# untitled.net
KiCad netlist of a schematic drawn in EAGLE
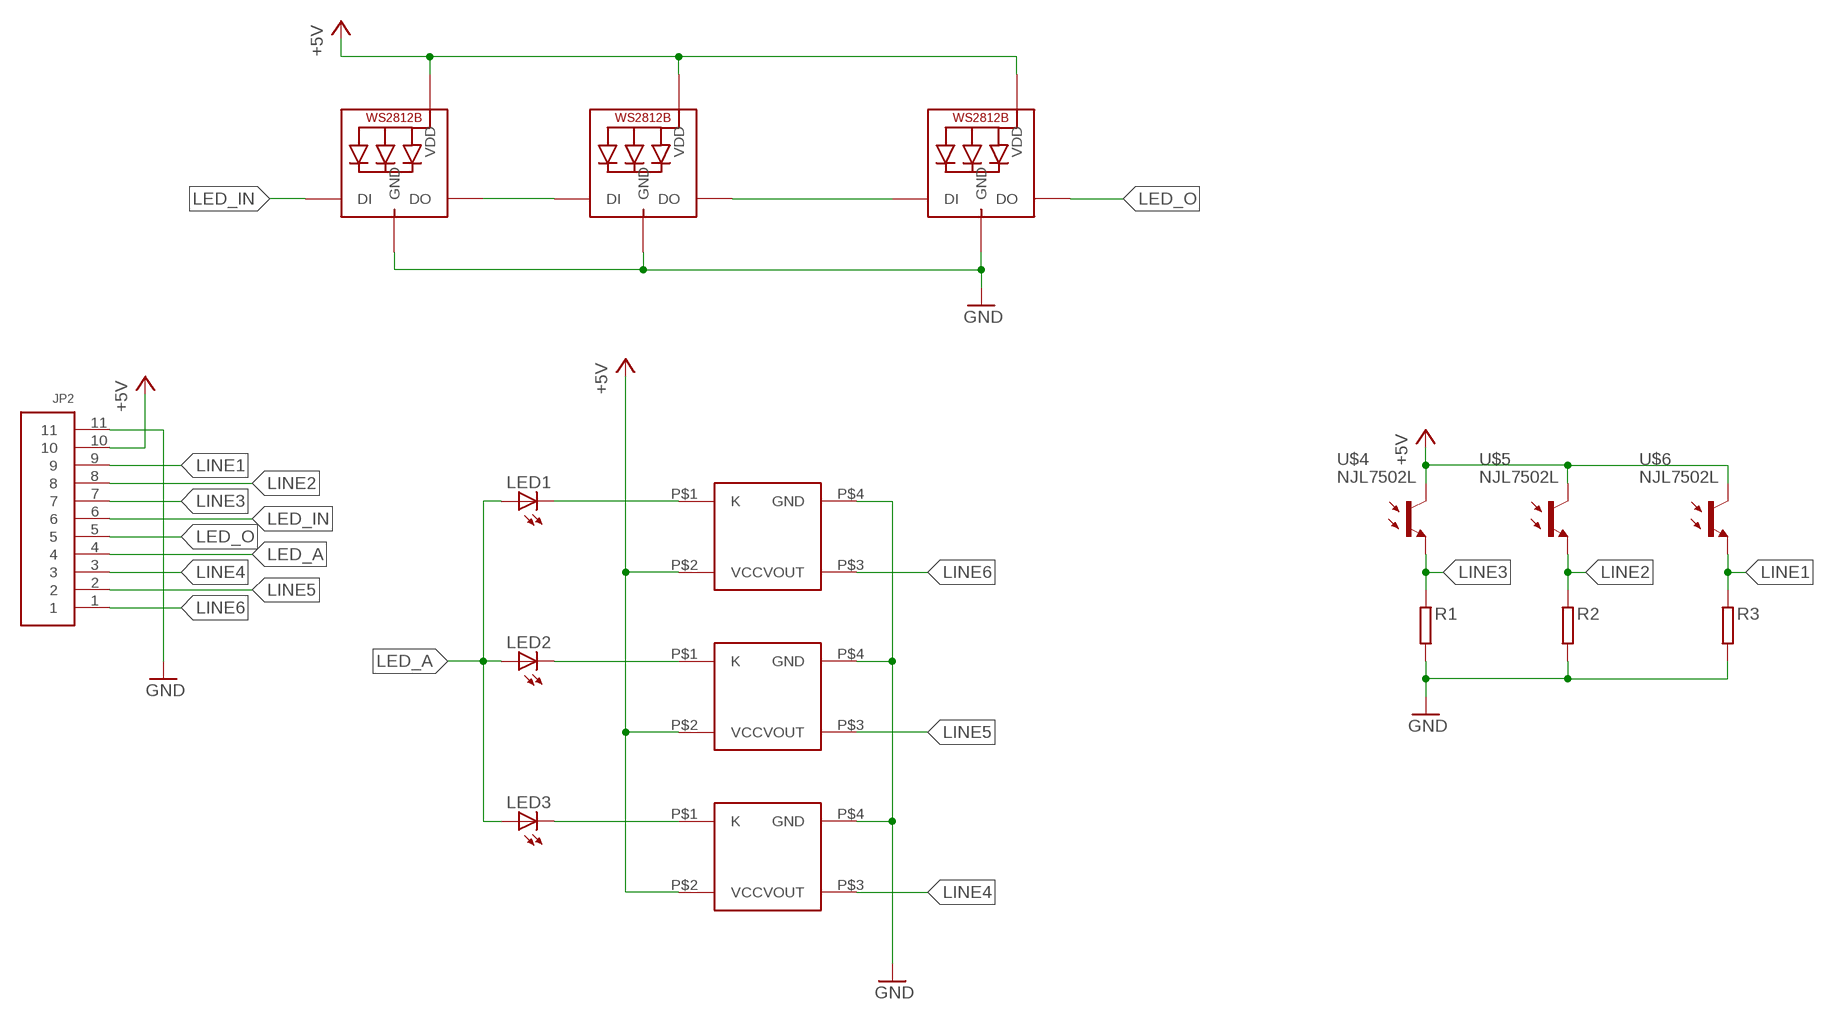
[diagram p0: schematic, sheet 1]

(export (version "E")
  (design (tool "Eeschema 10.0.6"))
  (components
    (comp (ref "JP2")
      (value "11PIN")
      (footprint "eagle-import:B11B-PH-K-S")
      (libsource (lib "eagle-import") (part "11PIN"))
    )
    (comp (ref "LED1")
      (value "LED5MM")
      (footprint "eagle-import:LED5MM")
      (libsource (lib "eagle-import") (part "LED5MM"))
    )
    (comp (ref "LED2")
      (value "LED5MM")
      (footprint "eagle-import:LED5MM")
      (libsource (lib "eagle-import") (part "LED5MM"))
    )
    (comp (ref "LED3")
      (value "LED5MM")
      (footprint "eagle-import:LED5MM")
      (libsource (lib "eagle-import") (part "LED5MM"))
    )
    (comp (ref "LED4")
      (value "WS2812B_5050N")
      (footprint "eagle-import:WS2812B-NARROW")
      (libsource (lib "eagle-import") (part "WS2812B_5050N"))
    )
    (comp (ref "LED5")
      (value "WS2812B_5050N")
      (footprint "eagle-import:WS2812B-NARROW")
      (libsource (lib "eagle-import") (part "WS2812B_5050N"))
    )
    (comp (ref "LED6")
      (value "WS2812B_5050N")
      (footprint "eagle-import:WS2812B-NARROW")
      (libsource (lib "eagle-import") (part "WS2812B_5050N"))
    )
    (comp (ref "R1")
      (value "RESISTOR1608")
      (footprint "eagle-import:SMD1608")
      (libsource (lib "eagle-import") (part "RESISTOR1608"))
    )
    (comp (ref "R2")
      (value "RESISTOR1608")
      (footprint "eagle-import:SMD1608")
      (libsource (lib "eagle-import") (part "RESISTOR1608"))
    )
    (comp (ref "R3")
      (value "RESISTOR1608")
      (footprint "eagle-import:SMD1608")
      (libsource (lib "eagle-import") (part "RESISTOR1608"))
    )
    (comp (ref "U$1")
      (value "S4282-51")
      (footprint "eagle-import:S4282-51")
      (libsource (lib "eagle-import") (part "S4282-51"))
    )
    (comp (ref "U$2")
      (value "S4282-51")
      (footprint "eagle-import:S4282-51")
      (libsource (lib "eagle-import") (part "S4282-51"))
    )
    (comp (ref "U$3")
      (value "S4282-51")
      (footprint "eagle-import:S4282-51")
      (libsource (lib "eagle-import") (part "S4282-51"))
    )
    (comp (ref "U$4")
      (value "NJL7502L")
      (footprint "eagle-import:NJL7502L")
      (libsource (lib "eagle-import") (part "NJL7502L"))
    )
    (comp (ref "U$5")
      (value "NJL7502L")
      (footprint "eagle-import:NJL7502L")
      (libsource (lib "eagle-import") (part "NJL7502L"))
    )
    (comp (ref "U$6")
      (value "NJL7502L")
      (footprint "eagle-import:NJL7502L")
      (libsource (lib "eagle-import") (part "NJL7502L"))
    )
  )
  (nets
    (net (code "1") (name "+5V") (class "Default")
      (node (ref "JP2") (pin "10") (pinfunction "10_10") (pintype "bidirectional"))
      (node (ref "LED4") (pin "1-VDD") (pinfunction "VDD_1-VDD") (pintype "power_in"))
      (node (ref "LED5") (pin "1-VDD") (pinfunction "VDD_1-VDD") (pintype "power_in"))
      (node (ref "LED6") (pin "1-VDD") (pinfunction "VDD_1-VDD") (pintype "power_in"))
      (node (ref "U$1") (pin "P$2") (pinfunction "VCC_P$2") (pintype "bidirectional"))
      (node (ref "U$2") (pin "P$2") (pinfunction "VCC_P$2") (pintype "bidirectional"))
      (node (ref "U$3") (pin "P$2") (pinfunction "VCC_P$2") (pintype "bidirectional"))
      (node (ref "U$4") (pin "C") (pinfunction "C_C") (pintype "passive"))
      (node (ref "U$5") (pin "C") (pinfunction "C_C") (pintype "passive"))
      (node (ref "U$6") (pin "C") (pinfunction "C_C") (pintype "passive"))
    )
    (net (code "2") (name "GND") (class "Default")
      (node (ref "JP2") (pin "11") (pinfunction "11_11") (pintype "bidirectional"))
      (node (ref "LED4") (pin "3-GND") (pinfunction "GND_3-GND") (pintype "power_in"))
      (node (ref "LED5") (pin "3-GND") (pinfunction "GND_3-GND") (pintype "power_in"))
      (node (ref "LED6") (pin "3-GND") (pinfunction "GND_3-GND") (pintype "power_in"))
      (node (ref "R1") (pin "2") (pinfunction "2_2") (pintype "passive"))
      (node (ref "R2") (pin "2") (pinfunction "2_2") (pintype "passive"))
      (node (ref "R3") (pin "2") (pinfunction "2_2") (pintype "passive"))
      (node (ref "U$1") (pin "P$4") (pinfunction "GND_P$4") (pintype "bidirectional"))
      (node (ref "U$2") (pin "P$4") (pinfunction "GND_P$4") (pintype "bidirectional"))
      (node (ref "U$3") (pin "P$4") (pinfunction "GND_P$4") (pintype "bidirectional"))
    )
    (net (code "3") (name "LED_A") (class "Default")
      (node (ref "JP2") (pin "4") (pinfunction "4_4") (pintype "bidirectional"))
      (node (ref "LED1") (pin "A") (pinfunction "A_A") (pintype "passive"))
      (node (ref "LED2") (pin "A") (pinfunction "A_A") (pintype "passive"))
      (node (ref "LED3") (pin "A") (pinfunction "A_A") (pintype "passive"))
    )
    (net (code "4") (name "LED_IN") (class "Default")
      (node (ref "JP2") (pin "6") (pinfunction "6_6") (pintype "bidirectional"))
      (node (ref "LED6") (pin "4-DIN") (pinfunction "DI_4-DIN") (pintype "input"))
    )
    (net (code "5") (name "LED_O") (class "Default")
      (node (ref "JP2") (pin "5") (pinfunction "5_5") (pintype "bidirectional"))
      (node (ref "LED4") (pin "2-DOUT") (pinfunction "DO_2-DOUT") (pintype "output"))
    )
    (net (code "6") (name "LINE1") (class "Default")
      (node (ref "JP2") (pin "9") (pinfunction "9_9") (pintype "bidirectional"))
      (node (ref "R3") (pin "1") (pinfunction "1_1") (pintype "passive"))
      (node (ref "U$6") (pin "E") (pinfunction "E_E") (pintype "passive"))
    )
    (net (code "7") (name "LINE2") (class "Default")
      (node (ref "JP2") (pin "8") (pinfunction "8_8") (pintype "bidirectional"))
      (node (ref "R2") (pin "1") (pinfunction "1_1") (pintype "passive"))
      (node (ref "U$5") (pin "E") (pinfunction "E_E") (pintype "passive"))
    )
    (net (code "8") (name "LINE3") (class "Default")
      (node (ref "JP2") (pin "7") (pinfunction "7_7") (pintype "bidirectional"))
      (node (ref "R1") (pin "1") (pinfunction "1_1") (pintype "passive"))
      (node (ref "U$4") (pin "E") (pinfunction "E_E") (pintype "passive"))
    )
    (net (code "9") (name "LINE4") (class "Default")
      (node (ref "JP2") (pin "3") (pinfunction "3_3") (pintype "bidirectional"))
      (node (ref "U$3") (pin "P$3") (pinfunction "VOUT_P$3") (pintype "bidirectional"))
    )
    (net (code "10") (name "LINE5") (class "Default")
      (node (ref "JP2") (pin "2") (pinfunction "2_2") (pintype "bidirectional"))
      (node (ref "U$2") (pin "P$3") (pinfunction "VOUT_P$3") (pintype "bidirectional"))
    )
    (net (code "11") (name "LINE6") (class "Default")
      (node (ref "JP2") (pin "1") (pinfunction "1_1") (pintype "bidirectional"))
      (node (ref "U$1") (pin "P$3") (pinfunction "VOUT_P$3") (pintype "bidirectional"))
    )
    (net (code "12") (name "Net-(LED1-C)") (class "Default")
      (node (ref "LED1") (pin "K") (pinfunction "C_K") (pintype "passive"))
      (node (ref "U$1") (pin "P$1") (pinfunction "K_P$1") (pintype "bidirectional"))
    )
    (net (code "13") (name "Net-(LED2-C)") (class "Default")
      (node (ref "LED2") (pin "K") (pinfunction "C_K") (pintype "passive"))
      (node (ref "U$2") (pin "P$1") (pinfunction "K_P$1") (pintype "bidirectional"))
    )
    (net (code "14") (name "Net-(LED3-C)") (class "Default")
      (node (ref "LED3") (pin "K") (pinfunction "C_K") (pintype "passive"))
      (node (ref "U$3") (pin "P$1") (pinfunction "K_P$1") (pintype "bidirectional"))
    )
    (net (code "15") (name "Net-(LED4-DI)") (class "Default")
      (node (ref "LED4") (pin "4-DIN") (pinfunction "DI_4-DIN") (pintype "input"))
      (node (ref "LED5") (pin "2-DOUT") (pinfunction "DO_2-DOUT") (pintype "output"))
    )
    (net (code "16") (name "Net-(LED5-DI)") (class "Default")
      (node (ref "LED5") (pin "4-DIN") (pinfunction "DI_4-DIN") (pintype "input"))
      (node (ref "LED6") (pin "2-DOUT") (pinfunction "DO_2-DOUT") (pintype "output"))
    )
  )
)
